# TT7-40_v1_1.net
KiCad netlist of a schematic drawn in EAGLE
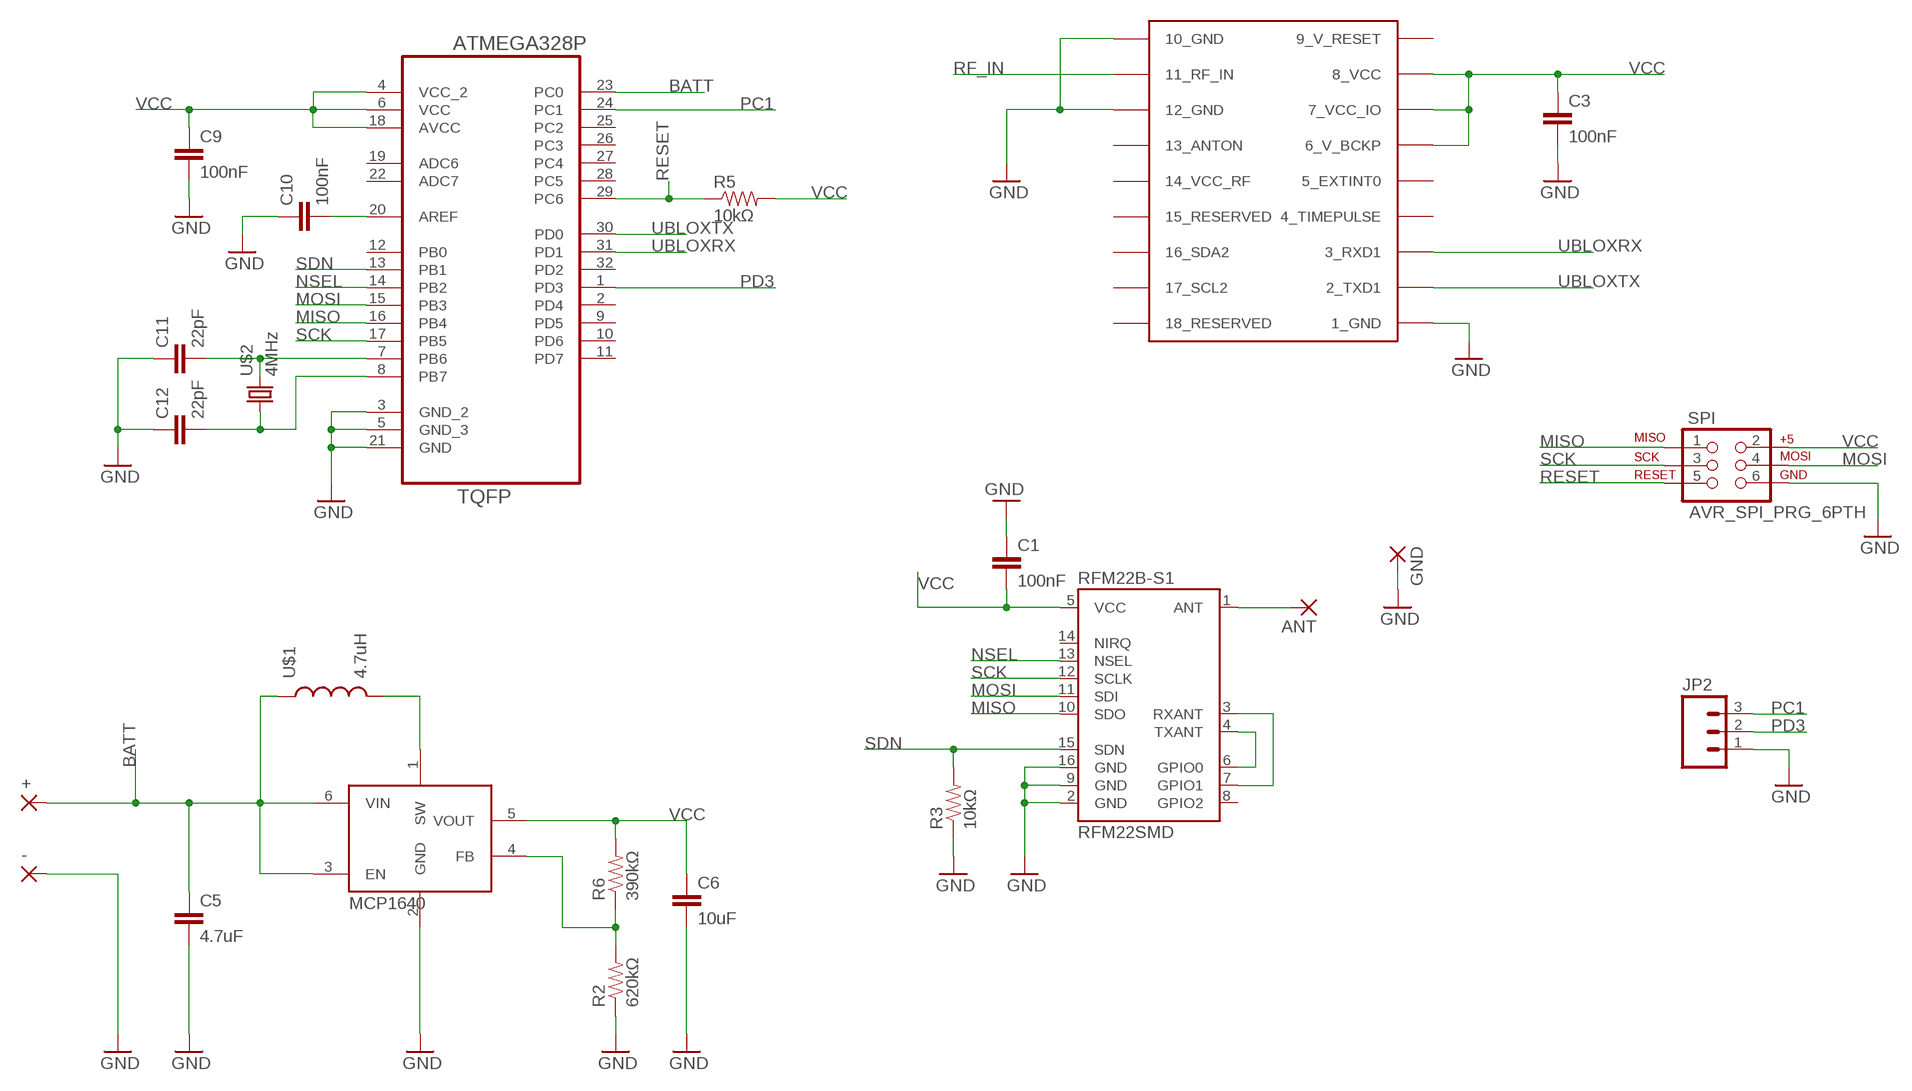
[diagram p0: schematic, sheet 1]

(export (version "E")
  (design (tool "Eeschema 10.0.6"))
  (components
    (comp (ref "+")
      (value "WIREPADSMD1,27-254")
      (footprint "eagle-import:SMD1,27-2,54")
      (libsource (lib "eagle-import") (part "WIREPADSMD1,27-254"))
    )
    (comp (ref "-")
      (value "WIREPADSMD1,27-254")
      (footprint "eagle-import:SMD1,27-2,54")
      (libsource (lib "eagle-import") (part "WIREPADSMD1,27-254"))
    )
    (comp (ref "ANT")
      (value "WIREPADSMD1,27-254")
      (footprint "eagle-import:SMD1,27-2,54")
      (libsource (lib "eagle-import") (part "WIREPADSMD1,27-254"))
    )
    (comp (ref "C1")
      (value "100nF")
      (footprint "eagle-import:1206")
      (libsource (lib "eagle-import") (part "CAP1206"))
    )
    (comp (ref "C3")
      (value "100nF")
      (footprint "eagle-import:1206")
      (libsource (lib "eagle-import") (part "CAP1206"))
    )
    (comp (ref "C5")
      (value "4.7uF")
      (footprint "eagle-import:1206")
      (libsource (lib "eagle-import") (part "CAP1206"))
    )
    (comp (ref "C6")
      (value "10uF")
      (footprint "eagle-import:1206")
      (libsource (lib "eagle-import") (part "CAP1206"))
    )
    (comp (ref "C9")
      (value "100nF")
      (footprint "eagle-import:1206")
      (libsource (lib "eagle-import") (part "CAP1206"))
    )
    (comp (ref "C10")
      (value "100nF")
      (footprint "eagle-import:1206")
      (libsource (lib "eagle-import") (part "CAP1206"))
    )
    (comp (ref "C11")
      (value "22pF")
      (footprint "eagle-import:0805")
      (libsource (lib "eagle-import") (part "CAP0805"))
    )
    (comp (ref "C12")
      (value "22pF")
      (footprint "eagle-import:0805")
      (libsource (lib "eagle-import") (part "CAP0805"))
    )
    (comp (ref "GND")
      (value "WIREPADSMD1,27-254")
      (footprint "eagle-import:SMD1,27-2,54")
      (libsource (lib "eagle-import") (part "WIREPADSMD1,27-254"))
    )
    (comp (ref "JP2")
      (value "M03PTH")
      (footprint "eagle-import:1X03")
      (libsource (lib "eagle-import") (part "M03PTH"))
    )
    (comp (ref "R2")
      (value "620kΩ")
      (footprint "eagle-import:0805")
      (libsource (lib "eagle-import") (part "SparkFun-Resistors_RESISTOR0805-RES"))
    )
    (comp (ref "R3")
      (value "10kΩ")
      (footprint "eagle-import:0603-RES")
      (libsource (lib "eagle-import") (part "RESISTOR0603-RES"))
    )
    (comp (ref "R5")
      (value "10kΩ")
      (footprint "eagle-import:0603-RES")
      (libsource (lib "eagle-import") (part "RESISTOR0603-RES"))
    )
    (comp (ref "R6")
      (value "390kΩ")
      (footprint "eagle-import:0805")
      (libsource (lib "eagle-import") (part "SparkFun-Resistors_RESISTOR0805-RES"))
    )
    (comp (ref "RFM22B-S1")
      (value "RFM22SMD")
      (footprint "eagle-import:RFM22-XXX-S2")
      (libsource (lib "eagle-import") (part "RFM22SMD"))
    )
    (comp (ref "SPI")
      (value "AVR_SPI_PRG_6PTH")
      (footprint "eagle-import:2X3")
      (libsource (lib "eagle-import") (part "AVR_SPI_PRG_6PTH"))
    )
    (comp (ref "U$1")
      (value "4.7uH")
      (footprint "eagle-import:DER0705")
      (libsource (lib "eagle-import") (part "DER07050705"))
    )
    (comp (ref "U$2")
      (value "4MHz")
      (footprint "eagle-import:ABM03_HC49")
      (libsource (lib "eagle-import") (part "ABRACON_ABM3_CRYSTALABM03_HC49"))
    )
    (comp (ref "U2")
      (value "MCP1640")
      (footprint "eagle-import:SOT23-6")
      (libsource (lib "eagle-import") (part "MCP1640"))
    )
    (comp (ref "U3")
      (value "ATMEGA328P-AU")
      (footprint "eagle-import:QFP80P900X900X120-32N")
      (libsource (lib "eagle-import") (part "ATMEGA328P-AU"))
    )
    (comp (ref "UBLOX-MAX7C")
      (value "UBLOX_MAX")
      (footprint "eagle-import:UBLOX_MAX")
      (libsource (lib "eagle-import") (part "UBLOX_MAX"))
    )
  )
  (nets
    (net (code "1") (name "/9_V_RESET") (class "Default")
      (node (ref "UBLOX-MAX7C") (pin "9_V_RESET") (pinfunction "9_V_RESET_9_V_RESET") (pintype "power_in"))
    )
    (net (code "2") (name "/BATT") (class "Default")
      (node (ref "+") (pin "1") (pinfunction "P_1") (pintype "passive"))
      (node (ref "C5") (pin "1") (pinfunction "1_1") (pintype "passive"))
      (node (ref "U$1") (pin "P$1") (pinfunction "1_P$1") (pintype "passive"))
      (node (ref "U2") (pin "3") (pinfunction "EN_3") (pintype "input"))
      (node (ref "U2") (pin "6") (pinfunction "VIN_6") (pintype "input"))
      (node (ref "U3") (pin "23") (pinfunction "PC0_23") (pintype "bidirectional"))
    )
    (net (code "3") (name "/MISO") (class "Default")
      (node (ref "RFM22B-S1") (pin "10") (pinfunction "SDO_10") (pintype "output"))
      (node (ref "SPI") (pin "1") (pinfunction "1_1") (pintype "passive"))
      (node (ref "U3") (pin "16") (pinfunction "PB4_16") (pintype "bidirectional"))
    )
    (net (code "4") (name "/MOSI") (class "Default")
      (node (ref "RFM22B-S1") (pin "11") (pinfunction "SDI_11") (pintype "input"))
      (node (ref "SPI") (pin "4") (pinfunction "4_4") (pintype "passive"))
      (node (ref "U3") (pin "15") (pinfunction "PB3_15") (pintype "bidirectional"))
    )
    (net (code "5") (name "/NSEL") (class "Default")
      (node (ref "RFM22B-S1") (pin "13") (pinfunction "NSEL_13") (pintype "input"))
      (node (ref "U3") (pin "14") (pinfunction "PB2_14") (pintype "bidirectional"))
    )
    (net (code "6") (name "/PC1") (class "Default")
      (node (ref "JP2") (pin "3") (pinfunction "3_3") (pintype "passive"))
      (node (ref "U3") (pin "24") (pinfunction "PC1_24") (pintype "bidirectional"))
    )
    (net (code "7") (name "/PD3") (class "Default")
      (node (ref "JP2") (pin "2") (pinfunction "2_2") (pintype "passive"))
      (node (ref "U3") (pin "1") (pinfunction "PD3_1") (pintype "bidirectional"))
    )
    (net (code "8") (name "/RESET") (class "Default")
      (node (ref "R5") (pin "1") (pinfunction "1_1") (pintype "passive"))
      (node (ref "SPI") (pin "5") (pinfunction "5_5") (pintype "passive"))
      (node (ref "U3") (pin "29") (pinfunction "PC6_29") (pintype "bidirectional"))
    )
    (net (code "9") (name "/RF_IN") (class "Default")
      (node (ref "UBLOX-MAX7C") (pin "11_RF_IN") (pinfunction "11_RF_IN_11_RF_IN") (pintype "bidirectional"))
    )
    (net (code "10") (name "/SCK") (class "Default")
      (node (ref "RFM22B-S1") (pin "12") (pinfunction "SCLK_12") (pintype "input"))
      (node (ref "SPI") (pin "3") (pinfunction "3_3") (pintype "passive"))
      (node (ref "U3") (pin "17") (pinfunction "PB5_17") (pintype "bidirectional"))
    )
    (net (code "11") (name "/SDN") (class "Default")
      (node (ref "R3") (pin "2") (pinfunction "2_2") (pintype "passive"))
      (node (ref "RFM22B-S1") (pin "15") (pinfunction "SDN_15") (pintype "input"))
      (node (ref "U3") (pin "13") (pinfunction "PB1_13") (pintype "bidirectional"))
    )
    (net (code "12") (name "/UBLOXRX") (class "Default")
      (node (ref "U3") (pin "31") (pinfunction "PD1_31") (pintype "bidirectional"))
      (node (ref "UBLOX-MAX7C") (pin "3_RXD1") (pinfunction "3_RXD1_3_RXD1") (pintype "bidirectional"))
    )
    (net (code "13") (name "/UBLOXTX") (class "Default")
      (node (ref "U3") (pin "30") (pinfunction "PD0_30") (pintype "bidirectional"))
      (node (ref "UBLOX-MAX7C") (pin "2_TXD1") (pinfunction "2_TXD1_2_TXD1") (pintype "bidirectional"))
    )
    (net (code "14") (name "/VCC") (class "Default")
      (node (ref "C1") (pin "2") (pinfunction "2_2") (pintype "passive"))
      (node (ref "C3") (pin "1") (pinfunction "1_1") (pintype "passive"))
      (node (ref "C6") (pin "1") (pinfunction "1_1") (pintype "passive"))
      (node (ref "C9") (pin "1") (pinfunction "1_1") (pintype "passive"))
      (node (ref "R5") (pin "2") (pinfunction "2_2") (pintype "passive"))
      (node (ref "R6") (pin "2") (pinfunction "2_2") (pintype "passive"))
      (node (ref "RFM22B-S1") (pin "5") (pinfunction "VCC_5") (pintype "bidirectional"))
      (node (ref "SPI") (pin "2") (pinfunction "2_2") (pintype "passive"))
      (node (ref "U2") (pin "5") (pinfunction "VOUT_5") (pintype "power_in"))
      (node (ref "U3") (pin "18") (pinfunction "AVCC_18") (pintype "power_in"))
      (node (ref "U3") (pin "4") (pinfunction "VCC_2_4") (pintype "power_in"))
      (node (ref "U3") (pin "6") (pinfunction "VCC_6") (pintype "power_in"))
      (node (ref "UBLOX-MAX7C") (pin "6_V_BCKP") (pinfunction "6_V_BCKP_6_V_BCKP") (pintype "bidirectional"))
      (node (ref "UBLOX-MAX7C") (pin "7_VCC_IO") (pinfunction "7_VCC_IO_7_VCC_IO") (pintype "power_in"))
      (node (ref "UBLOX-MAX7C") (pin "8_VCC") (pinfunction "8_VCC_8_VCC") (pintype "power_in"))
    )
    (net (code "15") (name "GND") (class "Default")
      (node (ref "-") (pin "1") (pinfunction "P_1") (pintype "passive"))
      (node (ref "C1") (pin "1") (pinfunction "1_1") (pintype "passive"))
      (node (ref "C10") (pin "1") (pinfunction "1_1") (pintype "passive"))
      (node (ref "C11") (pin "1") (pinfunction "1_1") (pintype "passive"))
      (node (ref "C12") (pin "1") (pinfunction "1_1") (pintype "passive"))
      (node (ref "C3") (pin "2") (pinfunction "2_2") (pintype "passive"))
      (node (ref "C5") (pin "2") (pinfunction "2_2") (pintype "passive"))
      (node (ref "C6") (pin "2") (pinfunction "2_2") (pintype "passive"))
      (node (ref "C9") (pin "2") (pinfunction "2_2") (pintype "passive"))
      (node (ref "GND") (pin "1") (pinfunction "P_1") (pintype "passive"))
      (node (ref "JP2") (pin "1") (pinfunction "1_1") (pintype "passive"))
      (node (ref "R2") (pin "1") (pinfunction "1_1") (pintype "passive"))
      (node (ref "R3") (pin "1") (pinfunction "1_1") (pintype "passive"))
      (node (ref "RFM22B-S1") (pin "16") (pinfunction "GND_16") (pintype "power_in"))
      (node (ref "RFM22B-S1") (pin "2") (pinfunction "GND_2") (pintype "power_in"))
      (node (ref "RFM22B-S1") (pin "9") (pinfunction "GND_9") (pintype "power_in"))
      (node (ref "SPI") (pin "6") (pinfunction "6_6") (pintype "passive"))
      (node (ref "U2") (pin "2") (pinfunction "GND_2") (pintype "power_in"))
      (node (ref "U3") (pin "21") (pinfunction "GND_21") (pintype "passive"))
      (node (ref "U3") (pin "3") (pinfunction "GND_2_3") (pintype "passive"))
      (node (ref "U3") (pin "5") (pinfunction "GND_3_5") (pintype "passive"))
      (node (ref "UBLOX-MAX7C") (pin "10_GND") (pinfunction "10_GND_10_GND") (pintype "power_in"))
      (node (ref "UBLOX-MAX7C") (pin "12_GND") (pinfunction "12_GND_12_GND") (pintype "power_in"))
      (node (ref "UBLOX-MAX7C") (pin "1_GND") (pinfunction "1_GND_1_GND") (pintype "power_in"))
    )
    (net (code "16") (name "Net-(ANT-P)") (class "Default")
      (node (ref "ANT") (pin "1") (pinfunction "P_1") (pintype "passive"))
      (node (ref "RFM22B-S1") (pin "1") (pinfunction "ANT_1") (pintype "bidirectional"))
    )
    (net (code "17") (name "Net-(RFM22B-S1-GPIO0)") (class "Default")
      (node (ref "RFM22B-S1") (pin "4") (pinfunction "TXANT_4") (pintype "input"))
      (node (ref "RFM22B-S1") (pin "6") (pinfunction "GPIO0_6") (pintype "bidirectional"))
    )
    (net (code "18") (name "Net-(RFM22B-S1-GPIO1)") (class "Default")
      (node (ref "RFM22B-S1") (pin "3") (pinfunction "RXANT_3") (pintype "input"))
      (node (ref "RFM22B-S1") (pin "7") (pinfunction "GPIO1_7") (pintype "bidirectional"))
    )
    (net (code "19") (name "Net-(U$1-2)") (class "Default")
      (node (ref "U$1") (pin "P$2") (pinfunction "2_P$2") (pintype "passive"))
      (node (ref "U2") (pin "1") (pinfunction "SW_1") (pintype "output"))
    )
    (net (code "20") (name "Net-(U2-FB)") (class "Default")
      (node (ref "R2") (pin "2") (pinfunction "2_2") (pintype "passive"))
      (node (ref "R6") (pin "1") (pinfunction "1_1") (pintype "passive"))
      (node (ref "U2") (pin "4") (pinfunction "FB_4") (pintype "input"))
    )
    (net (code "21") (name "Net-(U3-AREF)") (class "Default")
      (node (ref "C10") (pin "2") (pinfunction "2_2") (pintype "passive"))
      (node (ref "U3") (pin "20") (pinfunction "AREF_20") (pintype "input"))
    )
    (net (code "22") (name "Net-(U3-PB6)") (class "Default")
      (node (ref "C11") (pin "2") (pinfunction "2_2") (pintype "passive"))
      (node (ref "U$2") (pin "2") (pinfunction "2_2") (pintype "passive"))
      (node (ref "U3") (pin "7") (pinfunction "PB6_7") (pintype "bidirectional"))
    )
    (net (code "23") (name "Net-(U3-PB7)") (class "Default")
      (node (ref "C12") (pin "2") (pinfunction "2_2") (pintype "passive"))
      (node (ref "U$2") (pin "1") (pinfunction "1_1") (pintype "passive"))
      (node (ref "U3") (pin "8") (pinfunction "PB7_8") (pintype "bidirectional"))
    )
    (net (code "24") (name "unconnected-(RFM22B-S1-GPIO2-Pad8)") (class "Default")
      (node (ref "RFM22B-S1") (pin "8") (pinfunction "GPIO2_8") (pintype "bidirectional"))
    )
    (net (code "25") (name "unconnected-(RFM22B-S1-NIRQ-Pad14)") (class "Default")
      (node (ref "RFM22B-S1") (pin "14") (pinfunction "NIRQ_14") (pintype "output"))
    )
    (net (code "26") (name "unconnected-(U3-ADC6-Pad19)") (class "Default")
      (node (ref "U3") (pin "19") (pinfunction "ADC6_19") (pintype "input"))
    )
    (net (code "27") (name "unconnected-(U3-ADC7-Pad22)") (class "Default")
      (node (ref "U3") (pin "22") (pinfunction "ADC7_22") (pintype "input"))
    )
    (net (code "28") (name "unconnected-(U3-PB0-Pad12)") (class "Default")
      (node (ref "U3") (pin "12") (pinfunction "PB0_12") (pintype "bidirectional"))
    )
    (net (code "29") (name "unconnected-(U3-PC2-Pad25)") (class "Default")
      (node (ref "U3") (pin "25") (pinfunction "PC2_25") (pintype "bidirectional"))
    )
    (net (code "30") (name "unconnected-(U3-PC3-Pad26)") (class "Default")
      (node (ref "U3") (pin "26") (pinfunction "PC3_26") (pintype "bidirectional"))
    )
    (net (code "31") (name "unconnected-(U3-PC4-Pad27)") (class "Default")
      (node (ref "U3") (pin "27") (pinfunction "PC4_27") (pintype "bidirectional"))
    )
    (net (code "32") (name "unconnected-(U3-PC5-Pad28)") (class "Default")
      (node (ref "U3") (pin "28") (pinfunction "PC5_28") (pintype "bidirectional"))
    )
    (net (code "33") (name "unconnected-(U3-PD2-Pad32)") (class "Default")
      (node (ref "U3") (pin "32") (pinfunction "PD2_32") (pintype "bidirectional"))
    )
    (net (code "34") (name "unconnected-(U3-PD4-Pad2)") (class "Default")
      (node (ref "U3") (pin "2") (pinfunction "PD4_2") (pintype "bidirectional"))
    )
    (net (code "35") (name "unconnected-(U3-PD5-Pad9)") (class "Default")
      (node (ref "U3") (pin "9") (pinfunction "PD5_9") (pintype "bidirectional"))
    )
    (net (code "36") (name "unconnected-(U3-PD6-Pad10)") (class "Default")
      (node (ref "U3") (pin "10") (pinfunction "PD6_10") (pintype "bidirectional"))
    )
    (net (code "37") (name "unconnected-(U3-PD7-Pad11)") (class "Default")
      (node (ref "U3") (pin "11") (pinfunction "PD7_11") (pintype "bidirectional"))
    )
    (net (code "38") (name "unconnected-(UBLOX-MAX7C-Pad4_TIMEPULSE)") (class "Default")
      (node (ref "UBLOX-MAX7C") (pin "4_TIMEPULSE") (pinfunction "4_TIMEPULSE_4_TIMEPULSE") (pintype "bidirectional"))
    )
    (net (code "39") (name "unconnected-(UBLOX-MAX7C-Pad5_EXTINT0)") (class "Default")
      (node (ref "UBLOX-MAX7C") (pin "5_EXTINT0") (pinfunction "5_EXTINT0_5_EXTINT0") (pintype "bidirectional"))
    )
    (net (code "40") (name "unconnected-(UBLOX-MAX7C-Pad13_ANTON)") (class "Default")
      (node (ref "UBLOX-MAX7C") (pin "13_ANTON") (pinfunction "13_ANTON_13_ANTON") (pintype "bidirectional"))
    )
    (net (code "41") (name "unconnected-(UBLOX-MAX7C-Pad14_VCC_RF)") (class "Default")
      (node (ref "UBLOX-MAX7C") (pin "14_VCC_RF") (pinfunction "14_VCC_RF_14_VCC_RF") (pintype "bidirectional"))
    )
    (net (code "42") (name "unconnected-(UBLOX-MAX7C-Pad15_RESERVED)") (class "Default")
      (node (ref "UBLOX-MAX7C") (pin "15_RESERVED") (pinfunction "15_RESERVED_15_RESERVED") (pintype "bidirectional"))
    )
    (net (code "43") (name "unconnected-(UBLOX-MAX7C-Pad16_SDA2)") (class "Default")
      (node (ref "UBLOX-MAX7C") (pin "16_SDA2") (pinfunction "16_SDA2_16_SDA2") (pintype "bidirectional"))
    )
    (net (code "44") (name "unconnected-(UBLOX-MAX7C-Pad17_SCL2)") (class "Default")
      (node (ref "UBLOX-MAX7C") (pin "17_SCL2") (pinfunction "17_SCL2_17_SCL2") (pintype "bidirectional"))
    )
    (net (code "45") (name "unconnected-(UBLOX-MAX7C-Pad18_RESERVED)") (class "Default")
      (node (ref "UBLOX-MAX7C") (pin "18_RESERVED") (pinfunction "18_RESERVED_18_RESERVED") (pintype "bidirectional"))
    )
  )
)
